# slowik12.net
KiCad netlist of a schematic drawn in EAGLE
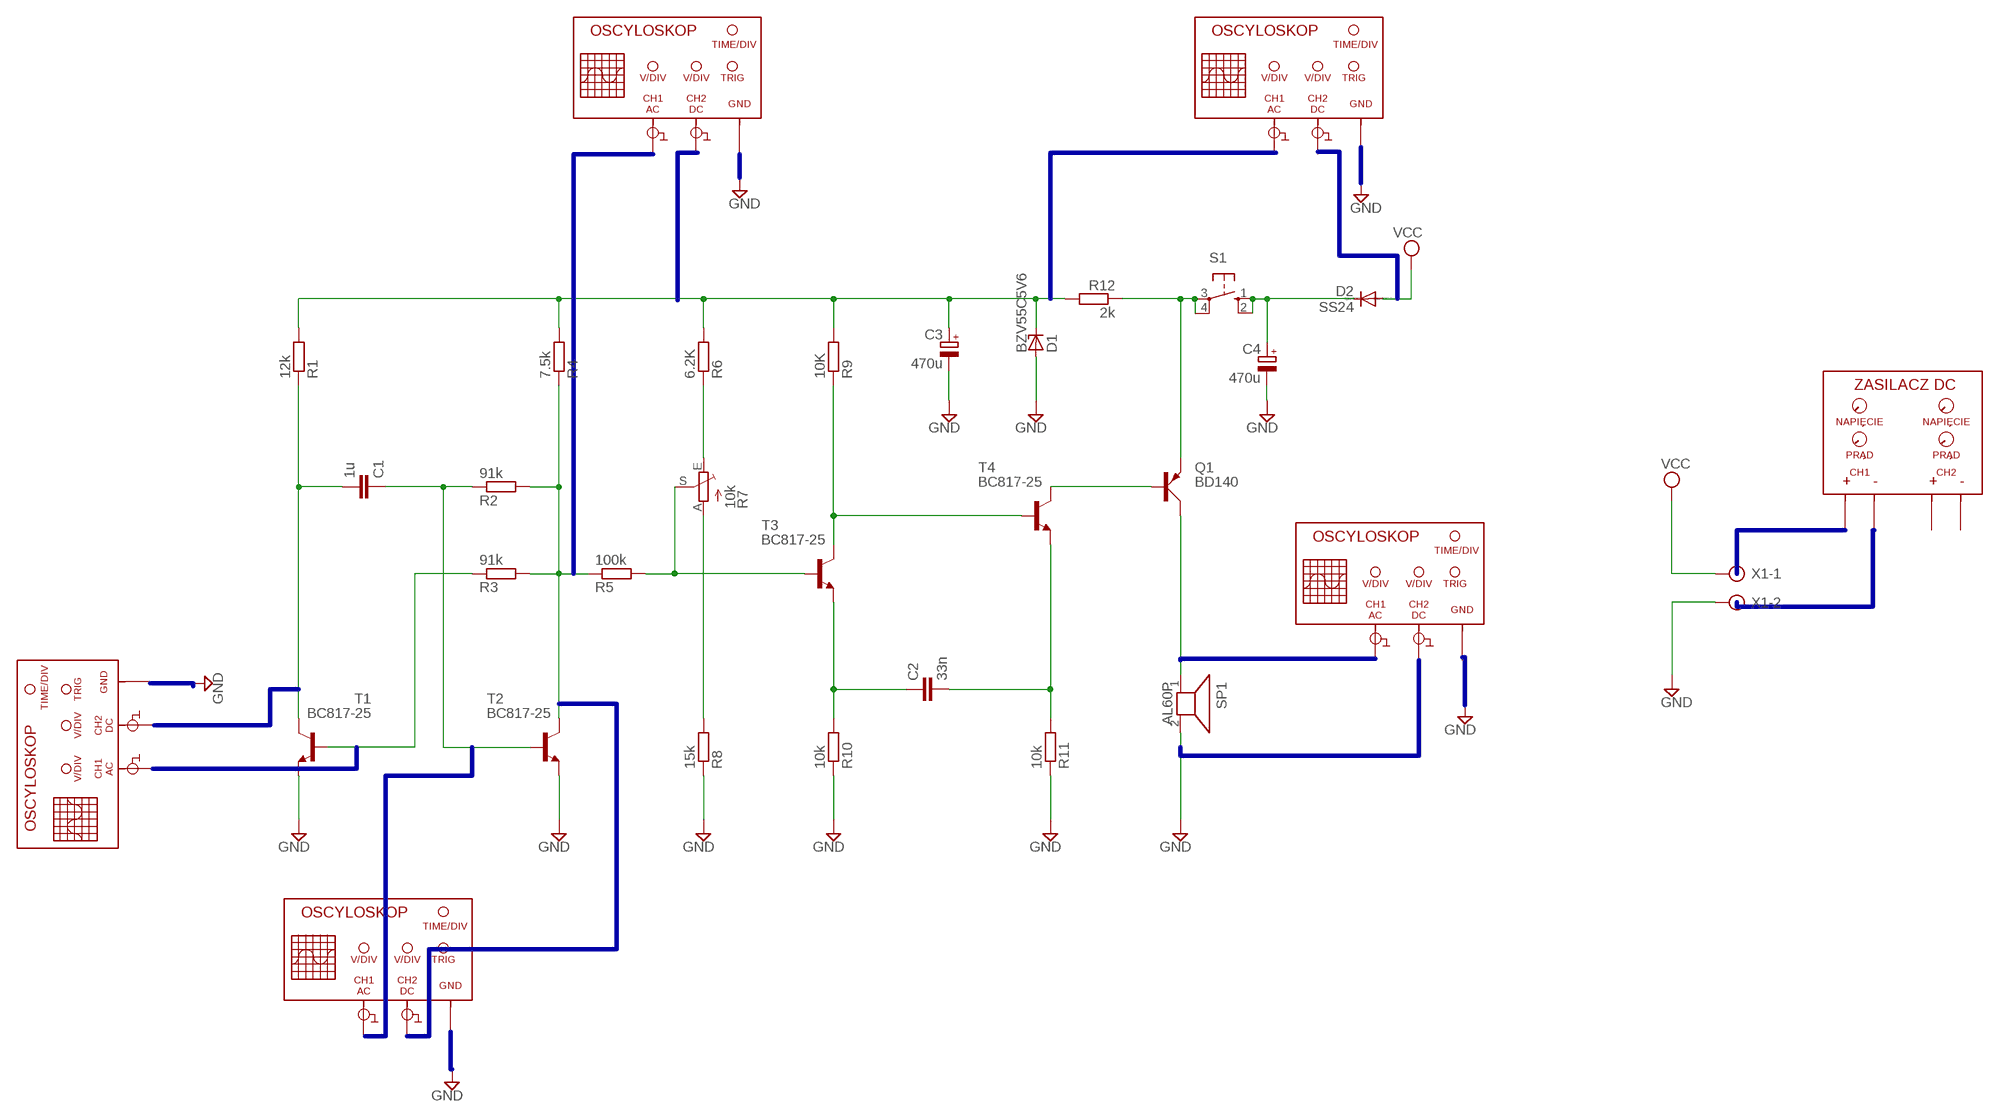
[diagram p0: schematic, sheet 1]

(export (version "E")
  (design (tool "Eeschema 10.0.6"))
  (components
    (comp (ref "C1")
      (value "1u")
      (footprint "eagle-import:C1206")
      (libsource (lib "eagle-import") (part "C-EUC1206"))
    )
    (comp (ref "C2")
      (value "33n")
      (footprint "eagle-import:C2.5-2")
      (libsource (lib "eagle-import") (part "C2.5/2"))
    )
    (comp (ref "C3")
      (value "470u")
      (footprint "eagle-import:E3,5-8")
      (libsource (lib "eagle-import") (part "CPOL-EUE3.5-8"))
    )
    (comp (ref "C4")
      (value "470u")
      (footprint "eagle-import:E3,5-8")
      (libsource (lib "eagle-import") (part "CPOL-EUE3.5-8"))
    )
    (comp (ref "D1")
      (value "BZV55C5V6")
      (footprint "eagle-import:SOD80C")
      (libsource (lib "eagle-import") (part "ZENER-DIODESOD80C"))
    )
    (comp (ref "D2")
      (value "SS24")
      (footprint "eagle-import:SMB")
      (libsource (lib "eagle-import") (part "ES2D"))
    )
    (comp (ref "Q1")
      (value "BD140")
      (footprint "eagle-import:TO126AV")
      (libsource (lib "eagle-import") (part "BD140"))
    )
    (comp (ref "R1")
      (value "12k")
      (footprint "eagle-import:R1206")
      (libsource (lib "eagle-import") (part "R-EU_R1206"))
    )
    (comp (ref "R2")
      (value "91k")
      (footprint "eagle-import:R1206")
      (libsource (lib "eagle-import") (part "R-EU_R1206"))
    )
    (comp (ref "R3")
      (value "91k")
      (footprint "eagle-import:R1206")
      (libsource (lib "eagle-import") (part "R-EU_R1206"))
    )
    (comp (ref "R4")
      (value "7.5k")
      (footprint "eagle-import:R1206")
      (libsource (lib "eagle-import") (part "R-EU_R1206"))
    )
    (comp (ref "R5")
      (value "100k")
      (footprint "eagle-import:R1206")
      (libsource (lib "eagle-import") (part "R-EU_R1206"))
    )
    (comp (ref "R6")
      (value "6.2K")
      (footprint "eagle-import:R1206")
      (libsource (lib "eagle-import") (part "R-EU_R1206"))
    )
    (comp (ref "R7")
      (value "10k")
      (footprint "eagle-import:PT-10")
      (libsource (lib "eagle-import") (part "TRIM_EU-PT10"))
    )
    (comp (ref "R8")
      (value "15k")
      (footprint "eagle-import:R1206")
      (libsource (lib "eagle-import") (part "R-EU_R1206"))
    )
    (comp (ref "R9")
      (value "10K")
      (footprint "eagle-import:R1206")
      (libsource (lib "eagle-import") (part "R-EU_R1206"))
    )
    (comp (ref "R10")
      (value "10k")
      (footprint "eagle-import:R1206")
      (libsource (lib "eagle-import") (part "R-EU_R1206"))
    )
    (comp (ref "R11")
      (value "10k")
      (footprint "eagle-import:R1206")
      (libsource (lib "eagle-import") (part "R-EU_R1206"))
    )
    (comp (ref "R12")
      (value "2k")
      (footprint "eagle-import:R1206")
      (libsource (lib "eagle-import") (part "R-EU_R1206"))
    )
    (comp (ref "S1")
      (value "10-XX")
      (footprint "eagle-import:B3F-10XX")
      (fields (field (name "MPN") "B3F-1000"))
      (libsource (lib "eagle-import") (part "10-XX"))
    )
    (comp (ref "SP1")
      (value "AL60P")
      (footprint "eagle-import:AL60P")
      (libsource (lib "eagle-import") (part "AL60P"))
    )
    (comp (ref "T1")
      (value "BC817-25")
      (footprint "eagle-import:SOT23-BEC")
      (libsource (lib "eagle-import") (part "-NPN-SOT23-BECBC817-25"))
    )
    (comp (ref "T2")
      (value "BC817-25")
      (footprint "eagle-import:SOT23-BEC")
      (libsource (lib "eagle-import") (part "-NPN-SOT23-BECBC817-25"))
    )
    (comp (ref "T3")
      (value "BC817-25")
      (footprint "eagle-import:SOT23-BEC")
      (libsource (lib "eagle-import") (part "-NPN-SOT23-BECBC817-25"))
    )
    (comp (ref "T4")
      (value "BC817-25")
      (footprint "eagle-import:SOT23-BEC")
      (libsource (lib "eagle-import") (part "-NPN-SOT23-BECBC817-25"))
    )
    (comp (ref "U$1")
      (value "OSCYLOSKOP_DC_DC")
      (footprint "eagle-import:OSCYLOSKOP")
      (libsource (lib "eagle-import") (part "OSCYLOSKOP_DC_DC"))
    )
    (comp (ref "U$2")
      (value "OSCYLOSKOP_DC_DC")
      (footprint "eagle-import:OSCYLOSKOP")
      (libsource (lib "eagle-import") (part "OSCYLOSKOP_DC_DC"))
    )
    (comp (ref "U$3")
      (value "ZASILACZ")
      (footprint "eagle-import:ZASILACZ")
      (libsource (lib "eagle-import") (part "ZASILACZ"))
    )
    (comp (ref "U$4")
      (value "OSCYLOSKOP_DC_DC")
      (footprint "eagle-import:OSCYLOSKOP")
      (libsource (lib "eagle-import") (part "OSCYLOSKOP_DC_DC"))
    )
    (comp (ref "U$5")
      (value "OSCYLOSKOP_DC_DC")
      (footprint "eagle-import:OSCYLOSKOP")
      (libsource (lib "eagle-import") (part "OSCYLOSKOP_DC_DC"))
    )
    (comp (ref "U$6")
      (value "OSCYLOSKOP_DC_DC")
      (footprint "eagle-import:OSCYLOSKOP")
      (libsource (lib "eagle-import") (part "OSCYLOSKOP_DC_DC"))
    )
    (comp (ref "X1")
      (value "AK500/2")
      (footprint "eagle-import:AK500_2")
      (libsource (lib "eagle-import") (part "AK500/2"))
    )
  )
  (nets
    (net (code "1") (name "GND") (class "Default")
      (node (ref "C3") (pin "-") (pinfunction "-_-") (pintype "passive"))
      (node (ref "C4") (pin "-") (pinfunction "-_-") (pintype "passive"))
      (node (ref "D1") (pin "A") (pinfunction "A_A") (pintype "passive"))
      (node (ref "R10") (pin "1") (pinfunction "1_1") (pintype "passive"))
      (node (ref "R11") (pin "1") (pinfunction "1_1") (pintype "passive"))
      (node (ref "R8") (pin "1") (pinfunction "1_1") (pintype "passive"))
      (node (ref "SP1") (pin "2") (pinfunction "2_2") (pintype "passive"))
      (node (ref "T1") (pin "E") (pinfunction "E_E") (pintype "passive"))
      (node (ref "T2") (pin "E") (pinfunction "E_E") (pintype "passive"))
      (node (ref "X1") (pin "2") (pinfunction "KL_2") (pintype "passive"))
    )
    (net (code "2") (name "Net-(C1-Pad1)") (class "Default")
      (node (ref "C1") (pin "1") (pinfunction "1_1") (pintype "passive"))
      (node (ref "R2") (pin "1") (pinfunction "1_1") (pintype "passive"))
      (node (ref "T2") (pin "B") (pinfunction "B_B") (pintype "passive"))
    )
    (net (code "3") (name "Net-(C1-Pad2)") (class "Default")
      (node (ref "C1") (pin "2") (pinfunction "2_2") (pintype "passive"))
      (node (ref "R1") (pin "1") (pinfunction "1_1") (pintype "passive"))
      (node (ref "T1") (pin "C") (pinfunction "C_C") (pintype "passive"))
    )
    (net (code "4") (name "Net-(C2-Pad1)") (class "Default")
      (node (ref "C2") (pin "1") (pinfunction "1_1") (pintype "passive"))
      (node (ref "R10") (pin "2") (pinfunction "2_2") (pintype "passive"))
      (node (ref "T3") (pin "E") (pinfunction "E_E") (pintype "passive"))
    )
    (net (code "5") (name "Net-(C2-Pad2)") (class "Default")
      (node (ref "C2") (pin "2") (pinfunction "2_2") (pintype "passive"))
      (node (ref "R11") (pin "2") (pinfunction "2_2") (pintype "passive"))
      (node (ref "T4") (pin "E") (pinfunction "E_E") (pintype "passive"))
    )
    (net (code "6") (name "Net-(C3-Pad+)") (class "Default")
      (node (ref "C3") (pin "+") (pinfunction "+_+") (pintype "passive"))
      (node (ref "D1") (pin "C") (pinfunction "C_C") (pintype "passive"))
      (node (ref "R1") (pin "2") (pinfunction "2_2") (pintype "passive"))
      (node (ref "R12") (pin "2") (pinfunction "2_2") (pintype "passive"))
      (node (ref "R4") (pin "2") (pinfunction "2_2") (pintype "passive"))
      (node (ref "R6") (pin "2") (pinfunction "2_2") (pintype "passive"))
      (node (ref "R9") (pin "2") (pinfunction "2_2") (pintype "passive"))
    )
    (net (code "7") (name "Net-(Q1-PadB)") (class "Default")
      (node (ref "Q1") (pin "B") (pinfunction "B_B") (pintype "passive"))
      (node (ref "T4") (pin "C") (pinfunction "C_C") (pintype "passive"))
    )
    (net (code "8") (name "Net-(Q1-PadC)") (class "Default")
      (node (ref "Q1") (pin "C") (pinfunction "C_C") (pintype "passive"))
      (node (ref "SP1") (pin "1") (pinfunction "1_1") (pintype "passive"))
    )
    (net (code "9") (name "Net-(R2-Pad2)") (class "Default")
      (node (ref "R2") (pin "2") (pinfunction "2_2") (pintype "passive"))
      (node (ref "R3") (pin "2") (pinfunction "2_2") (pintype "passive"))
      (node (ref "R4") (pin "1") (pinfunction "1_1") (pintype "passive"))
      (node (ref "R5") (pin "1") (pinfunction "1_1") (pintype "passive"))
      (node (ref "T2") (pin "C") (pinfunction "C_C") (pintype "passive"))
    )
    (net (code "10") (name "Net-(R3-Pad1)") (class "Default")
      (node (ref "R3") (pin "1") (pinfunction "1_1") (pintype "passive"))
      (node (ref "T1") (pin "B") (pinfunction "B_B") (pintype "passive"))
    )
    (net (code "11") (name "Net-(R5-Pad2)") (class "Default")
      (node (ref "R5") (pin "2") (pinfunction "2_2") (pintype "passive"))
      (node (ref "R7") (pin "S") (pinfunction "S_S") (pintype "passive"))
      (node (ref "T3") (pin "B") (pinfunction "B_B") (pintype "passive"))
    )
    (net (code "12") (name "Net-(R6-Pad1)") (class "Default")
      (node (ref "R6") (pin "1") (pinfunction "1_1") (pintype "passive"))
      (node (ref "R7") (pin "E") (pinfunction "E_E") (pintype "passive"))
    )
    (net (code "13") (name "Net-(R7-PadA)") (class "Default")
      (node (ref "R7") (pin "A") (pinfunction "A_A") (pintype "passive"))
      (node (ref "R8") (pin "2") (pinfunction "2_2") (pintype "passive"))
    )
    (net (code "14") (name "Net-(R9-Pad1)") (class "Default")
      (node (ref "R9") (pin "1") (pinfunction "1_1") (pintype "passive"))
      (node (ref "T3") (pin "C") (pinfunction "C_C") (pintype "passive"))
      (node (ref "T4") (pin "B") (pinfunction "B_B") (pintype "passive"))
    )
    (net (code "15") (name "Net-(S1-P)") (class "Default")
      (node (ref "Q1") (pin "E") (pinfunction "E_E") (pintype "passive"))
      (node (ref "R12") (pin "1") (pinfunction "1_1") (pintype "passive"))
      (node (ref "S1") (pin "3") (pinfunction "P_3") (pintype "passive"))
      (node (ref "S1") (pin "4") (pinfunction "P1_4") (pintype "passive"))
    )
    (net (code "16") (name "Net-(S1-S)") (class "Default")
      (node (ref "C4") (pin "+") (pinfunction "+_+") (pintype "passive"))
      (node (ref "D2") (pin "C") (pinfunction "C_C") (pintype "passive"))
      (node (ref "S1") (pin "1") (pinfunction "S_1") (pintype "passive"))
      (node (ref "S1") (pin "2") (pinfunction "S1_2") (pintype "passive"))
    )
    (net (code "17") (name "VCC") (class "Default")
      (node (ref "D2") (pin "A") (pinfunction "A_A") (pintype "passive"))
      (node (ref "X1") (pin "1") (pinfunction "KL_1") (pintype "passive"))
    )
    (net (code "18") (name "unconnected-(U$1-PadCH1)") (class "Default")
      (node (ref "U$1") (pin "CH1") (pinfunction "CH1_CH1") (pintype "bidirectional"))
    )
    (net (code "19") (name "unconnected-(U$1-PadCH2)") (class "Default")
      (node (ref "U$1") (pin "CH2") (pinfunction "CH2_CH2") (pintype "bidirectional"))
    )
    (net (code "20") (name "unconnected-(U$1-PadGND)") (class "Default")
      (node (ref "U$1") (pin "GND") (pinfunction "GND_GND") (pintype "bidirectional"))
    )
    (net (code "21") (name "unconnected-(U$2-PadCH1)") (class "Default")
      (node (ref "U$2") (pin "CH1") (pinfunction "CH1_CH1") (pintype "bidirectional"))
    )
    (net (code "22") (name "unconnected-(U$2-PadCH2)") (class "Default")
      (node (ref "U$2") (pin "CH2") (pinfunction "CH2_CH2") (pintype "bidirectional"))
    )
    (net (code "23") (name "unconnected-(U$2-PadGND)") (class "Default")
      (node (ref "U$2") (pin "GND") (pinfunction "GND_GND") (pintype "bidirectional"))
    )
    (net (code "24") (name "unconnected-(U$3-CH1+-PadC1+)") (class "Default")
      (node (ref "U$3") (pin "C1+") (pinfunction "CH1+_C1+") (pintype "bidirectional"))
    )
    (net (code "25") (name "unconnected-(U$3-CH1--PadC1-)") (class "Default")
      (node (ref "U$3") (pin "C1-") (pinfunction "CH1-_C1-") (pintype "bidirectional"))
    )
    (net (code "26") (name "unconnected-(U$3-CH2+-PadC2+)") (class "Default")
      (node (ref "U$3") (pin "C2+") (pinfunction "CH2+_C2+") (pintype "bidirectional"))
    )
    (net (code "27") (name "unconnected-(U$3-CH2--PadC2-)") (class "Default")
      (node (ref "U$3") (pin "C2-") (pinfunction "CH2-_C2-") (pintype "bidirectional"))
    )
    (net (code "28") (name "unconnected-(U$4-PadCH1)") (class "Default")
      (node (ref "U$4") (pin "CH1") (pinfunction "CH1_CH1") (pintype "bidirectional"))
    )
    (net (code "29") (name "unconnected-(U$4-PadCH2)") (class "Default")
      (node (ref "U$4") (pin "CH2") (pinfunction "CH2_CH2") (pintype "bidirectional"))
    )
    (net (code "30") (name "unconnected-(U$4-PadGND)") (class "Default")
      (node (ref "U$4") (pin "GND") (pinfunction "GND_GND") (pintype "bidirectional"))
    )
    (net (code "31") (name "unconnected-(U$5-PadCH1)") (class "Default")
      (node (ref "U$5") (pin "CH1") (pinfunction "CH1_CH1") (pintype "bidirectional"))
    )
    (net (code "32") (name "unconnected-(U$5-PadCH2)") (class "Default")
      (node (ref "U$5") (pin "CH2") (pinfunction "CH2_CH2") (pintype "bidirectional"))
    )
    (net (code "33") (name "unconnected-(U$5-PadGND)") (class "Default")
      (node (ref "U$5") (pin "GND") (pinfunction "GND_GND") (pintype "bidirectional"))
    )
    (net (code "34") (name "unconnected-(U$6-PadCH1)") (class "Default")
      (node (ref "U$6") (pin "CH1") (pinfunction "CH1_CH1") (pintype "bidirectional"))
    )
    (net (code "35") (name "unconnected-(U$6-PadCH2)") (class "Default")
      (node (ref "U$6") (pin "CH2") (pinfunction "CH2_CH2") (pintype "bidirectional"))
    )
    (net (code "36") (name "unconnected-(U$6-PadGND)") (class "Default")
      (node (ref "U$6") (pin "GND") (pinfunction "GND_GND") (pintype "bidirectional"))
    )
  )
)
